# mit_radar_r2_layout.net
KiCad netlist of a schematic drawn in EAGLE
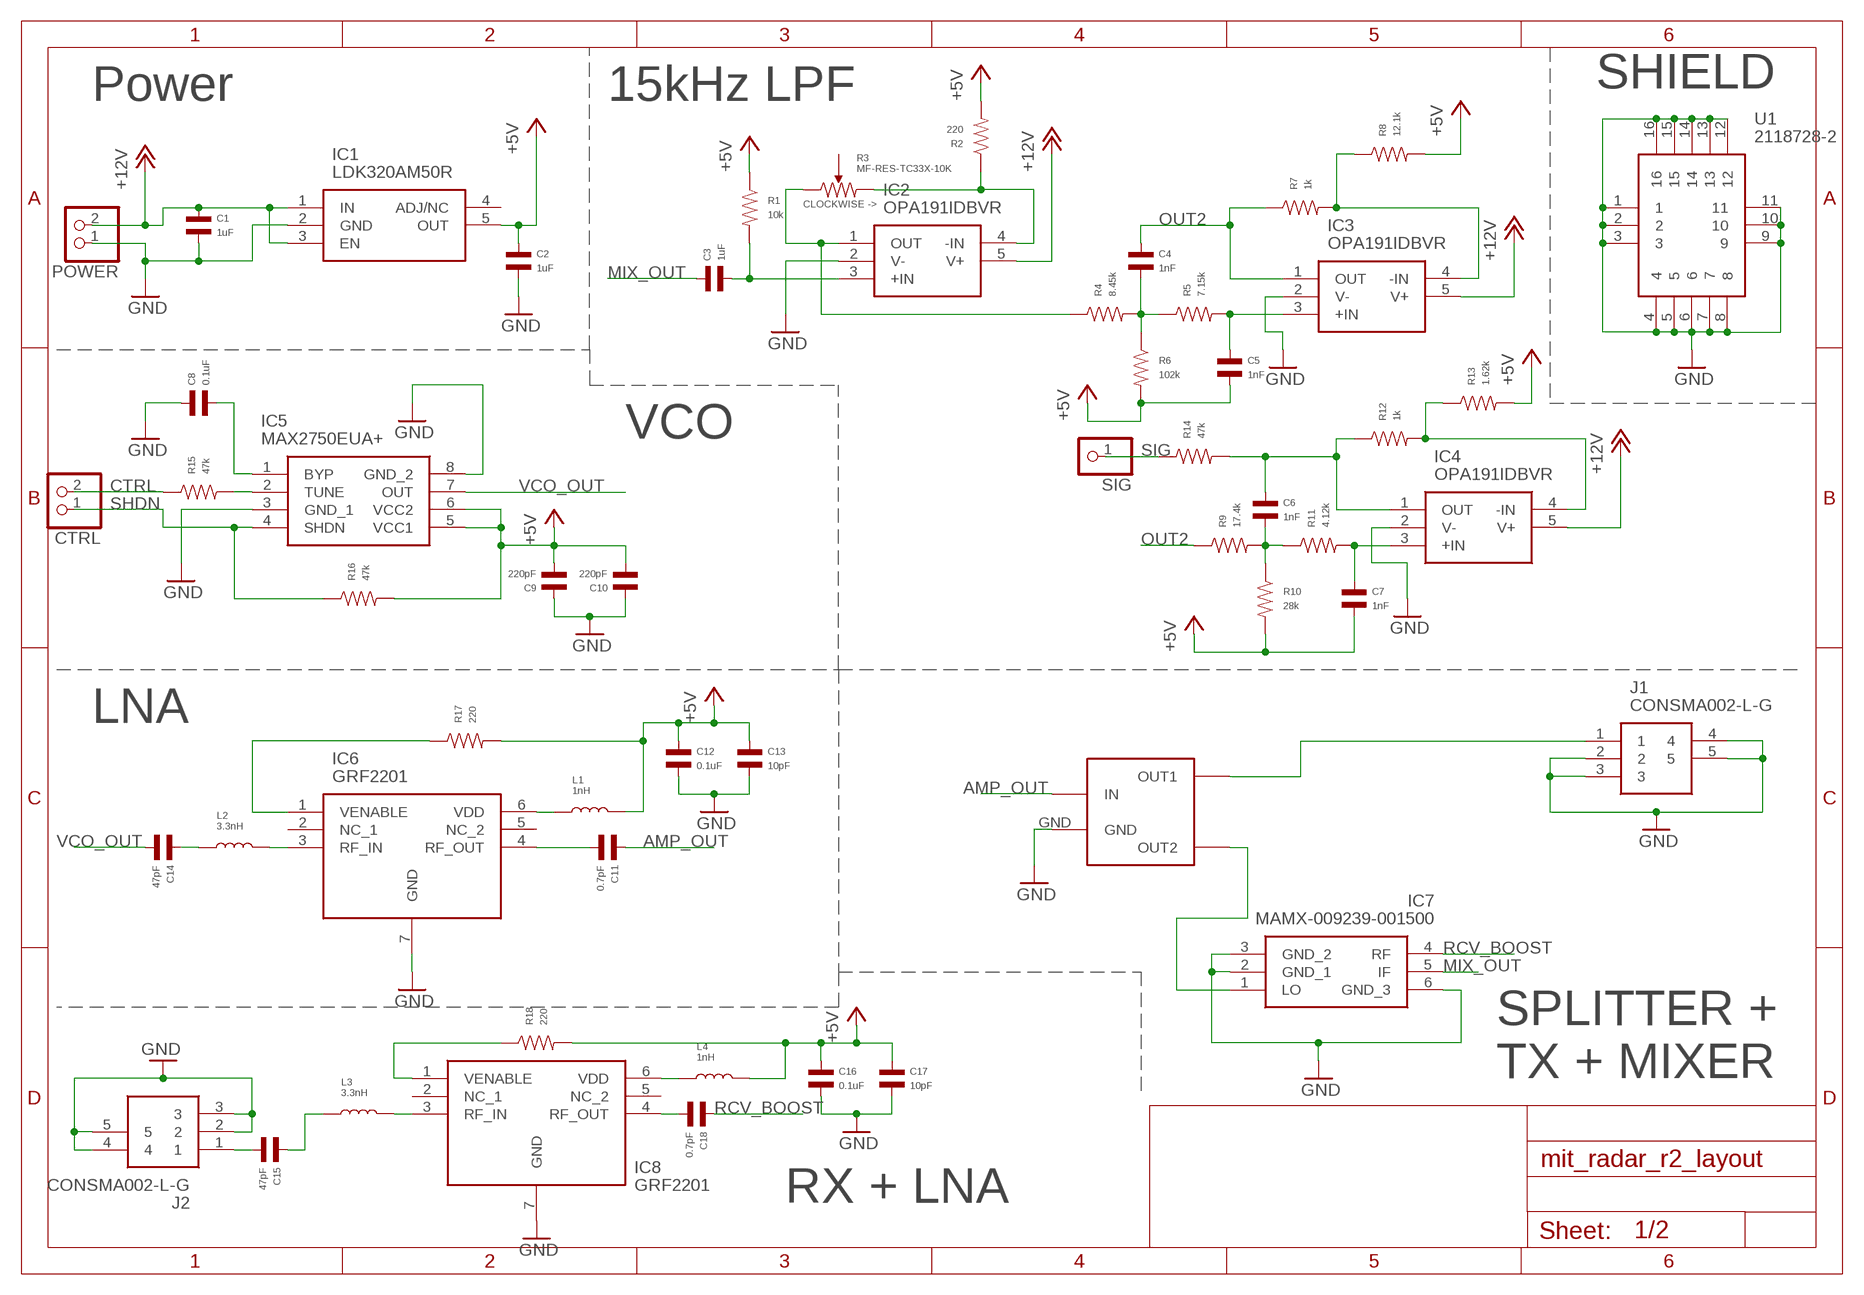
[diagram p0: schematic, sheet 1]
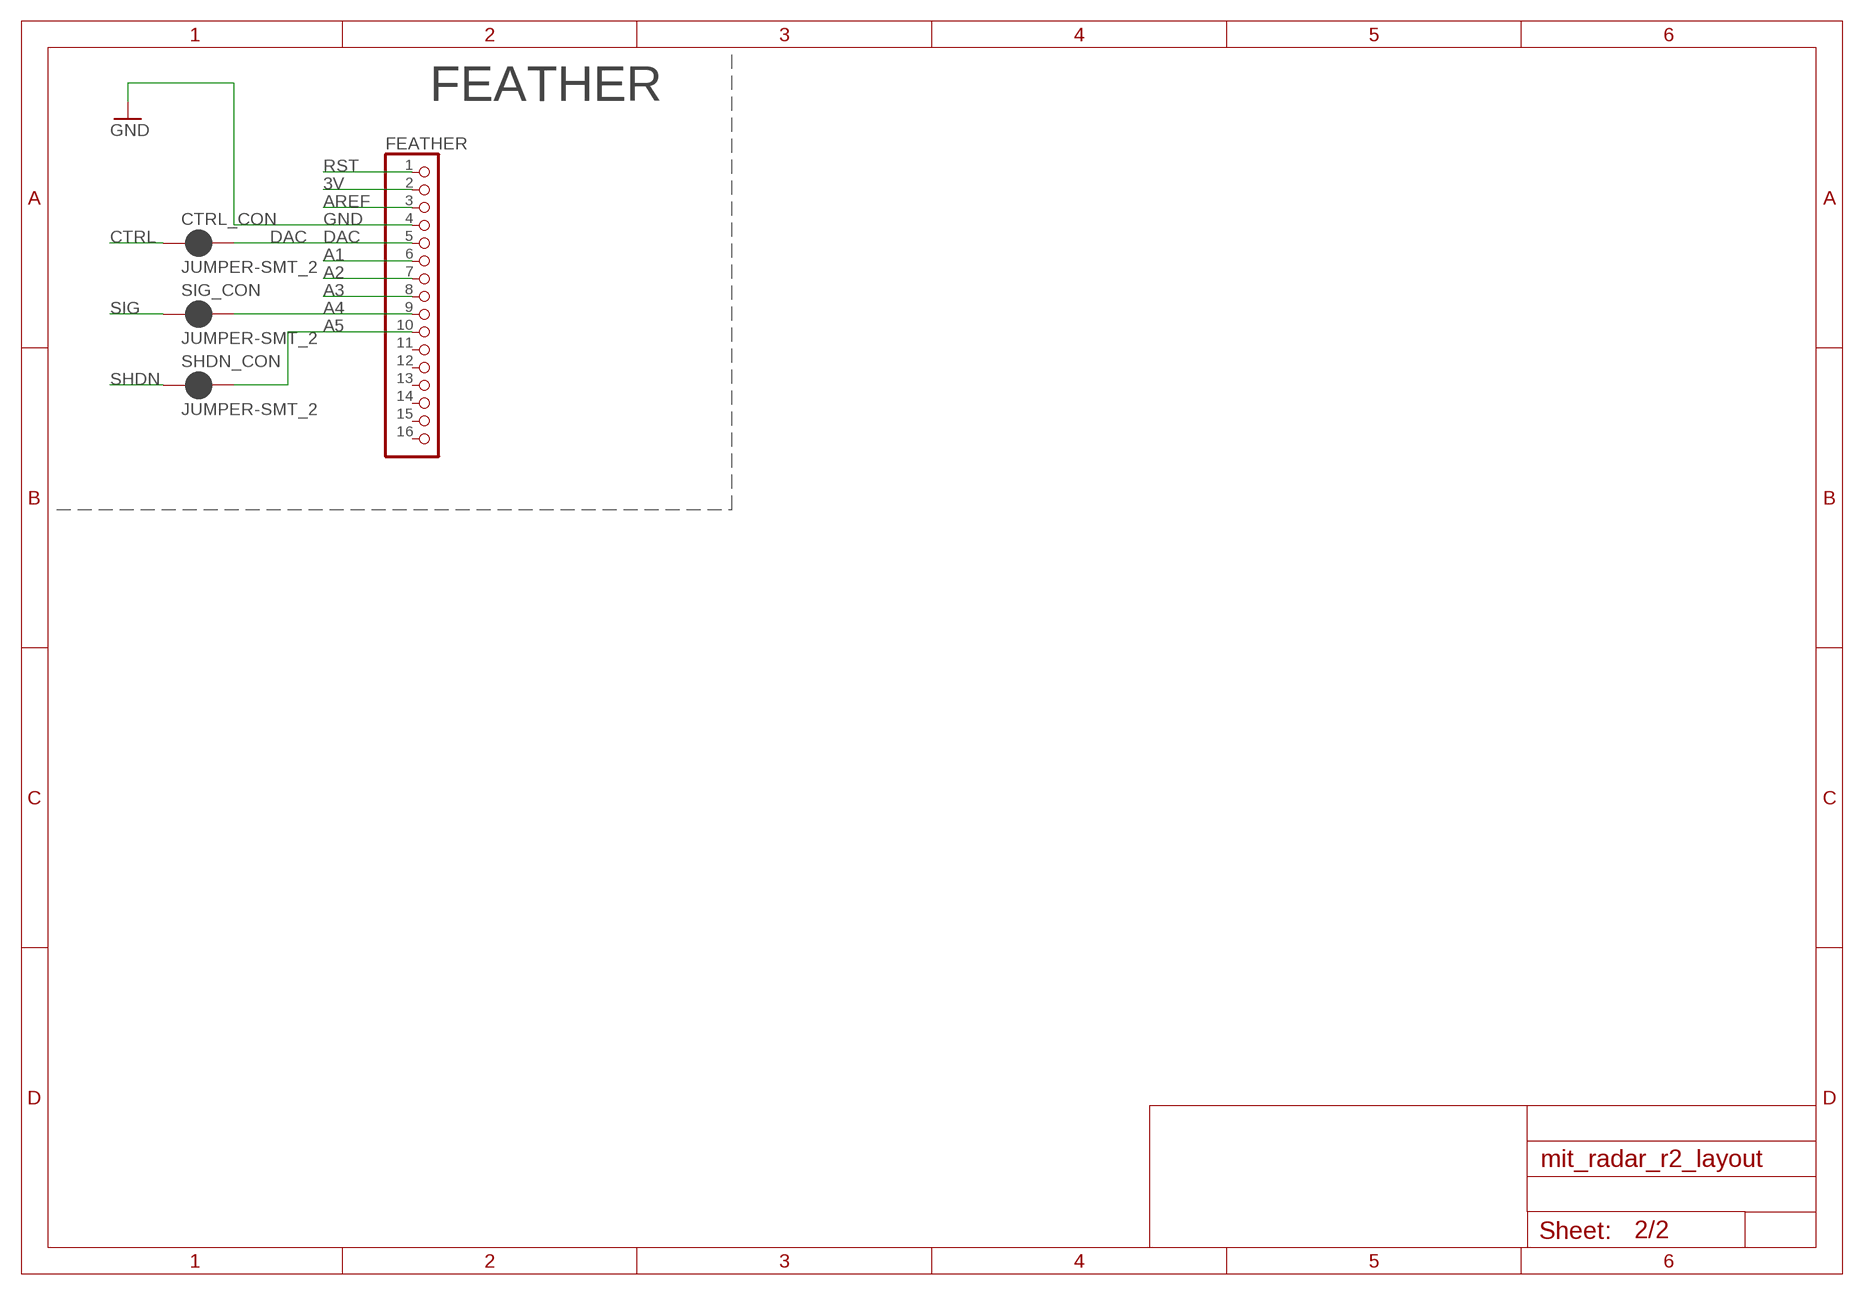
[diagram p1: schematic, sheet 2]

(export (version "E")
  (design (tool "Eeschema 10.0.6"))
  (components
    (comp (ref "C1")
      (value "1uF")
      (footprint "eagle-import:C0402")
      (libsource (lib "eagle-import") (part "CAPACITOR_NP_0402"))
    )
    (comp (ref "C2")
      (value "1uF")
      (footprint "eagle-import:C0402")
      (libsource (lib "eagle-import") (part "CAPACITOR_NP_0402"))
    )
    (comp (ref "C3")
      (value "1uF")
      (footprint "eagle-import:C0402")
      (libsource (lib "eagle-import") (part "CAPACITOR_NP_0402"))
    )
    (comp (ref "C4")
      (value "1nF")
      (footprint "eagle-import:C0402")
      (libsource (lib "eagle-import") (part "CAPACITOR_NP_0402"))
    )
    (comp (ref "C5")
      (value "1nF")
      (footprint "eagle-import:C0402")
      (libsource (lib "eagle-import") (part "CAPACITOR_NP_0402"))
    )
    (comp (ref "C6")
      (value "1nF")
      (footprint "eagle-import:C0402")
      (libsource (lib "eagle-import") (part "CAPACITOR_NP_0402"))
    )
    (comp (ref "C7")
      (value "1nF")
      (footprint "eagle-import:C0402")
      (libsource (lib "eagle-import") (part "CAPACITOR_NP_0402"))
    )
    (comp (ref "C8")
      (value "0.1uF")
      (footprint "eagle-import:C0402")
      (libsource (lib "eagle-import") (part "CAPACITOR_NP_0402"))
    )
    (comp (ref "C9")
      (value "220pF")
      (footprint "eagle-import:C0402")
      (libsource (lib "eagle-import") (part "CAPACITOR_NP_0402"))
    )
    (comp (ref "C10")
      (value "220pF")
      (footprint "eagle-import:C0402")
      (libsource (lib "eagle-import") (part "CAPACITOR_NP_0402"))
    )
    (comp (ref "C11")
      (value "0.7pF")
      (footprint "eagle-import:C0402")
      (libsource (lib "eagle-import") (part "CAPACITOR_NP_0402"))
    )
    (comp (ref "C12")
      (value "0.1uF")
      (footprint "eagle-import:C0402")
      (libsource (lib "eagle-import") (part "CAPACITOR_NP_0402"))
    )
    (comp (ref "C13")
      (value "10pF")
      (footprint "eagle-import:C0402")
      (libsource (lib "eagle-import") (part "CAPACITOR_NP_0402"))
    )
    (comp (ref "C14")
      (value "47pF")
      (footprint "eagle-import:C0402")
      (libsource (lib "eagle-import") (part "CAPACITOR_NP_0402"))
    )
    (comp (ref "C15")
      (value "47pF")
      (footprint "eagle-import:C0402")
      (libsource (lib "eagle-import") (part "CAPACITOR_NP_0402"))
    )
    (comp (ref "C16")
      (value "0.1uF")
      (footprint "eagle-import:C0402")
      (libsource (lib "eagle-import") (part "CAPACITOR_NP_0402"))
    )
    (comp (ref "C17")
      (value "10pF")
      (footprint "eagle-import:C0402")
      (libsource (lib "eagle-import") (part "CAPACITOR_NP_0402"))
    )
    (comp (ref "C18")
      (value "0.7pF")
      (footprint "eagle-import:C0402")
      (libsource (lib "eagle-import") (part "CAPACITOR_NP_0402"))
    )
    (comp (ref "CTRL")
      (value "PINHD-1X2")
      (footprint "eagle-import:1X02")
      (libsource (lib "eagle-import") (part "PINHD-1X2"))
    )
    (comp (ref "IC1")
      (value "LDK320AM50R")
      (footprint "eagle-import:SOT95P280X145-5N")
      (fields (field (name "MOUSER_PART_NUMBER") "511-LDK320AM50R"))
      (libsource (lib "eagle-import") (part "LDK320AM50R"))
    )
    (comp (ref "IC2")
      (value "OPA191IDBVR")
      (footprint "eagle-import:SOT95P280X145-5N")
      (fields (field (name "MOUSER_PART_NUMBER") "595-OPA191IDBVR"))
      (libsource (lib "eagle-import") (part "OPA191IDBVR"))
    )
    (comp (ref "IC3")
      (value "OPA191IDBVR")
      (footprint "eagle-import:SOT95P280X145-5N")
      (fields (field (name "MOUSER_PART_NUMBER") "595-OPA191IDBVR"))
      (libsource (lib "eagle-import") (part "OPA191IDBVR"))
    )
    (comp (ref "IC4")
      (value "OPA191IDBVR")
      (footprint "eagle-import:SOT95P280X145-5N")
      (fields (field (name "MOUSER_PART_NUMBER") "595-OPA191IDBVR"))
      (libsource (lib "eagle-import") (part "OPA191IDBVR"))
    )
    (comp (ref "IC5")
      (value "MAX2750EUA+")
      (footprint "eagle-import:SOP65P490X110-8N")
      (fields (field (name "MOUSER_PART_NUMBER") "700-MAX2750EUA") (field (name "RS_PART_NUMBER") "1898516P"))
      (libsource (lib "eagle-import") (part "MAX2750EUA+"))
    )
    (comp (ref "IC6")
      (value "GRF2201")
      (footprint "eagle-import:SON50P150X150X50-7N")
      (fields (field (name "MOUSER_PART_NUMBER") "459-GRF2201"))
      (libsource (lib "eagle-import") (part "GRF2201"))
    )
    (comp (ref "IC7")
      (value "MAMX-009239-001500")
      (footprint "eagle-import:MAMX009239001500")
      (fields (field (name "MOUSER_PART_NUMBER") "937-MAMX-9239-001500"))
      (libsource (lib "eagle-import") (part "MAMX-009239-001500"))
    )
    (comp (ref "IC8")
      (value "GRF2201")
      (footprint "eagle-import:SON50P150X150X50-7N")
      (fields (field (name "MOUSER_PART_NUMBER") "459-GRF2201"))
      (libsource (lib "eagle-import") (part "GRF2201"))
    )
    (comp (ref "J1")
      (value "CONSMA002-L-G")
      (footprint "eagle-import:CONSMA002LG")
      (fields (field (name "MOUSER_PART_NUMBER") "712-CONSMA002-L-G"))
      (libsource (lib "eagle-import") (part "CONSMA002-L-G"))
    )
    (comp (ref "J2")
      (value "CONSMA002-L-G")
      (footprint "eagle-import:CONSMA002LG")
      (fields (field (name "MOUSER_PART_NUMBER") "712-CONSMA002-L-G"))
      (libsource (lib "eagle-import") (part "CONSMA002-L-G"))
    )
    (comp (ref "L1")
      (value "1nH")
      (footprint "eagle-import:L0402")
      (libsource (lib "eagle-import") (part "INDUCTOR_0402"))
    )
    (comp (ref "L2")
      (value "3.3nH")
      (footprint "eagle-import:L0402")
      (libsource (lib "eagle-import") (part "INDUCTOR_0402"))
    )
    (comp (ref "L3")
      (value "3.3nH")
      (footprint "eagle-import:L0402")
      (libsource (lib "eagle-import") (part "INDUCTOR_0402"))
    )
    (comp (ref "L4")
      (value "1nH")
      (footprint "eagle-import:L0402")
      (libsource (lib "eagle-import") (part "INDUCTOR_0402"))
    )
    (comp (ref "POWER")
      (value "PINHD-1X2")
      (footprint "eagle-import:1X02")
      (libsource (lib "eagle-import") (part "PINHD-1X2"))
    )
    (comp (ref "R1")
      (value "10k")
      (footprint "eagle-import:R0402")
      (libsource (lib "eagle-import") (part "RESISTOR_0402"))
    )
    (comp (ref "R2")
      (value "220")
      (footprint "eagle-import:R0402")
      (libsource (lib "eagle-import") (part "RESISTOR_0402"))
    )
    (comp (ref "R3")
      (value "MF-RES-TC33X-10K")
      (footprint "eagle-import:TC33")
      (fields (field (name "HOUSEPART") "YES") (field (name "TOLERANCE") "25%"))
      (libsource (lib "eagle-import") (part "POTENTIOMETER_TC33_10K"))
    )
    (comp (ref "R4")
      (value "8.45k")
      (footprint "eagle-import:R0402")
      (libsource (lib "eagle-import") (part "RESISTOR_0402"))
    )
    (comp (ref "R5")
      (value "7.15k")
      (footprint "eagle-import:R0402")
      (libsource (lib "eagle-import") (part "RESISTOR_0402"))
    )
    (comp (ref "R6")
      (value "102k")
      (footprint "eagle-import:R0402")
      (libsource (lib "eagle-import") (part "RESISTOR_0402"))
    )
    (comp (ref "R7")
      (value "1k")
      (footprint "eagle-import:R0402")
      (libsource (lib "eagle-import") (part "RESISTOR_0402"))
    )
    (comp (ref "R8")
      (value "12.1k")
      (footprint "eagle-import:R0402")
      (libsource (lib "eagle-import") (part "RESISTOR_0402"))
    )
    (comp (ref "R9")
      (value "17.4k")
      (footprint "eagle-import:R0402")
      (libsource (lib "eagle-import") (part "RESISTOR_0402"))
    )
    (comp (ref "R10")
      (value "28k")
      (footprint "eagle-import:R0402")
      (libsource (lib "eagle-import") (part "RESISTOR_0402"))
    )
    (comp (ref "R11")
      (value "4.12k")
      (footprint "eagle-import:R0402")
      (libsource (lib "eagle-import") (part "RESISTOR_0402"))
    )
    (comp (ref "R12")
      (value "1k")
      (footprint "eagle-import:R0402")
      (libsource (lib "eagle-import") (part "RESISTOR_0402"))
    )
    (comp (ref "R13")
      (value "1.62k")
      (footprint "eagle-import:R0402")
      (libsource (lib "eagle-import") (part "RESISTOR_0402"))
    )
    (comp (ref "R14")
      (value "47k")
      (footprint "eagle-import:R0402")
      (libsource (lib "eagle-import") (part "RESISTOR_0402"))
    )
    (comp (ref "R15")
      (value "47k")
      (footprint "eagle-import:R0402")
      (libsource (lib "eagle-import") (part "RESISTOR_0402"))
    )
    (comp (ref "R16")
      (value "47k")
      (footprint "eagle-import:R0402")
      (libsource (lib "eagle-import") (part "RESISTOR_0402"))
    )
    (comp (ref "R17")
      (value "220")
      (footprint "eagle-import:R0402")
      (libsource (lib "eagle-import") (part "RESISTOR_0402"))
    )
    (comp (ref "R18")
      (value "220")
      (footprint "eagle-import:R0402")
      (libsource (lib "eagle-import") (part "RESISTOR_0402"))
    )
    (comp (ref "SIG")
      (value "PINHD-1X1")
      (footprint "eagle-import:1X01")
      (libsource (lib "eagle-import") (part "PINHD-1X1"))
    )
    (comp (ref "U$1")
      (value "PS3216GT2-R50-T1")
      (footprint "eagle-import:PS3216GT2-R50-T1")
      (libsource (lib "eagle-import") (part "PS3216GT2-R50-T1"))
    )
    (comp (ref "U1")
      (value "2118728-2")
      (footprint "eagle-import:21187282")
      (fields (field (name "MOUSER_PART_NUMBER") "571-2118728-2") (field (name "RS_PART_NUMBER") "1720955"))
      (libsource (lib "eagle-import") (part "2118728-2"))
    )
    (comp (ref "CTRL_CON")
      (value "JUMPER-SMT_2")
      (footprint "eagle-import:SMT-JUMPER_2_NC_PASTE_NO-SILK")
      (libsource (lib "eagle-import") (part "JUMPER-SMT_2_NC_PASTE_NO-SILK"))
    )
    (comp (ref "FEATHER")
      (value "PINHD-1X16")
      (footprint "eagle-import:1X16")
      (libsource (lib "eagle-import") (part "PINHD-1X16"))
    )
    (comp (ref "SHDN_CON")
      (value "JUMPER-SMT_2")
      (footprint "eagle-import:SMT-JUMPER_2_NC_PASTE_NO-SILK")
      (libsource (lib "eagle-import") (part "JUMPER-SMT_2_NC_PASTE_NO-SILK"))
    )
    (comp (ref "SIG_CON")
      (value "JUMPER-SMT_2")
      (footprint "eagle-import:SMT-JUMPER_2_NC_PASTE_NO-SILK")
      (libsource (lib "eagle-import") (part "JUMPER-SMT_2_NC_PASTE_NO-SILK"))
    )
  )
  (nets
    (net (code "1") (name "+5V") (class "Default")
      (node (ref "C10") (pin "P$2") (pinfunction "P$2_P$2") (pintype "passive"))
      (node (ref "C12") (pin "P$1") (pinfunction "P$1_P$1") (pintype "passive"))
      (node (ref "C13") (pin "P$1") (pinfunction "P$1_P$1") (pintype "passive"))
      (node (ref "C16") (pin "P$1") (pinfunction "P$1_P$1") (pintype "passive"))
      (node (ref "C17") (pin "P$1") (pinfunction "P$1_P$1") (pintype "passive"))
      (node (ref "C2") (pin "P$1") (pinfunction "P$1_P$1") (pintype "passive"))
      (node (ref "C5") (pin "P$2") (pinfunction "P$2_P$2") (pintype "passive"))
      (node (ref "C7") (pin "P$2") (pinfunction "P$2_P$2") (pintype "passive"))
      (node (ref "C9") (pin "P$2") (pinfunction "P$2_P$2") (pintype "passive"))
      (node (ref "IC1") (pin "5") (pinfunction "OUT_5") (pintype "bidirectional"))
      (node (ref "IC5") (pin "5") (pinfunction "VCC1_5") (pintype "bidirectional"))
      (node (ref "IC5") (pin "6") (pinfunction "VCC2_6") (pintype "bidirectional"))
      (node (ref "L1") (pin "P$2") (pinfunction "P$2_P$2") (pintype "passive"))
      (node (ref "L4") (pin "P$2") (pinfunction "P$2_P$2") (pintype "passive"))
      (node (ref "R1") (pin "P$1") (pinfunction "P$1_P$1") (pintype "passive"))
      (node (ref "R10") (pin "P$2") (pinfunction "P$2_P$2") (pintype "passive"))
      (node (ref "R13") (pin "P$2") (pinfunction "P$2_P$2") (pintype "passive"))
      (node (ref "R16") (pin "P$2") (pinfunction "P$2_P$2") (pintype "passive"))
      (node (ref "R17") (pin "P$2") (pinfunction "P$2_P$2") (pintype "passive"))
      (node (ref "R18") (pin "P$2") (pinfunction "P$2_P$2") (pintype "passive"))
      (node (ref "R2") (pin "P$2") (pinfunction "P$2_P$2") (pintype "passive"))
      (node (ref "R6") (pin "P$2") (pinfunction "P$2_P$2") (pintype "passive"))
      (node (ref "R8") (pin "P$2") (pinfunction "P$2_P$2") (pintype "passive"))
    )
    (net (code "2") (name "+12V") (class "Default")
      (node (ref "C1") (pin "P$1") (pinfunction "P$1_P$1") (pintype "passive"))
      (node (ref "IC1") (pin "1") (pinfunction "IN_1") (pintype "bidirectional"))
      (node (ref "IC1") (pin "3") (pinfunction "EN_3") (pintype "bidirectional"))
      (node (ref "IC2") (pin "5") (pinfunction "V+_5") (pintype "bidirectional"))
      (node (ref "IC3") (pin "5") (pinfunction "V+_5") (pintype "bidirectional"))
      (node (ref "IC4") (pin "5") (pinfunction "V+_5") (pintype "bidirectional"))
      (node (ref "POWER") (pin "2") (pinfunction "2_2") (pintype "passive"))
    )
    (net (code "3") (name "3V") (class "Default")
      (node (ref "FEATHER") (pin "2") (pinfunction "2_2") (pintype "passive"))
    )
    (net (code "4") (name "A1") (class "Default")
      (node (ref "FEATHER") (pin "6") (pinfunction "6_6") (pintype "passive"))
    )
    (net (code "5") (name "A2") (class "Default")
      (node (ref "FEATHER") (pin "7") (pinfunction "7_7") (pintype "passive"))
    )
    (net (code "6") (name "A3") (class "Default")
      (node (ref "FEATHER") (pin "8") (pinfunction "8_8") (pintype "passive"))
    )
    (net (code "7") (name "A4") (class "Default")
      (node (ref "FEATHER") (pin "9") (pinfunction "9_9") (pintype "passive"))
      (node (ref "SIG_CON") (pin "2") (pinfunction "2_2") (pintype "passive"))
    )
    (net (code "8") (name "A5") (class "Default")
      (node (ref "FEATHER") (pin "10") (pinfunction "10_10") (pintype "passive"))
      (node (ref "SHDN_CON") (pin "2") (pinfunction "2_2") (pintype "passive"))
    )
    (net (code "9") (name "AMP_OUT") (class "Default")
      (node (ref "C11") (pin "P$1") (pinfunction "P$1_P$1") (pintype "passive"))
      (node (ref "U$1") (pin "IN") (pinfunction "IN_IN") (pintype "bidirectional"))
    )
    (net (code "10") (name "AREF") (class "Default")
      (node (ref "FEATHER") (pin "3") (pinfunction "3_3") (pintype "passive"))
    )
    (net (code "11") (name "CTRL") (class "Default")
      (node (ref "CTRL") (pin "2") (pinfunction "2_2") (pintype "passive"))
      (node (ref "CTRL_CON") (pin "1") (pinfunction "1_1") (pintype "passive"))
      (node (ref "R15") (pin "P$1") (pinfunction "P$1_P$1") (pintype "passive"))
    )
    (net (code "12") (name "DAC") (class "Default")
      (node (ref "CTRL_CON") (pin "2") (pinfunction "2_2") (pintype "passive"))
      (node (ref "FEATHER") (pin "5") (pinfunction "5_5") (pintype "passive"))
    )
    (net (code "13") (name "GND") (class "Default")
      (node (ref "C1") (pin "P$2") (pinfunction "P$2_P$2") (pintype "passive"))
      (node (ref "C10") (pin "P$1") (pinfunction "P$1_P$1") (pintype "passive"))
      (node (ref "C12") (pin "P$2") (pinfunction "P$2_P$2") (pintype "passive"))
      (node (ref "C13") (pin "P$2") (pinfunction "P$2_P$2") (pintype "passive"))
      (node (ref "C16") (pin "P$2") (pinfunction "P$2_P$2") (pintype "passive"))
      (node (ref "C17") (pin "P$2") (pinfunction "P$2_P$2") (pintype "passive"))
      (node (ref "C2") (pin "P$2") (pinfunction "P$2_P$2") (pintype "passive"))
      (node (ref "C8") (pin "P$1") (pinfunction "P$1_P$1") (pintype "passive"))
      (node (ref "C9") (pin "P$1") (pinfunction "P$1_P$1") (pintype "passive"))
      (node (ref "FEATHER") (pin "4") (pinfunction "4_4") (pintype "passive"))
      (node (ref "IC1") (pin "2") (pinfunction "GND_2") (pintype "bidirectional"))
      (node (ref "IC2") (pin "2") (pinfunction "V-_2") (pintype "bidirectional"))
      (node (ref "IC3") (pin "2") (pinfunction "V-_2") (pintype "bidirectional"))
      (node (ref "IC4") (pin "2") (pinfunction "V-_2") (pintype "bidirectional"))
      (node (ref "IC5") (pin "3") (pinfunction "GND_1_3") (pintype "bidirectional"))
      (node (ref "IC5") (pin "8") (pinfunction "GND_2_8") (pintype "bidirectional"))
      (node (ref "IC6") (pin "7") (pinfunction "GND_7") (pintype "bidirectional"))
      (node (ref "IC7") (pin "2") (pinfunction "GND_1_2") (pintype "bidirectional"))
      (node (ref "IC7") (pin "3") (pinfunction "GND_2_3") (pintype "bidirectional"))
      (node (ref "IC7") (pin "6") (pinfunction "GND_3_6") (pintype "bidirectional"))
      (node (ref "IC8") (pin "7") (pinfunction "GND_7") (pintype "bidirectional"))
      (node (ref "J1") (pin "2") (pinfunction "2_2") (pintype "bidirectional"))
      (node (ref "J1") (pin "3") (pinfunction "3_3") (pintype "bidirectional"))
      (node (ref "J1") (pin "4") (pinfunction "4_4") (pintype "bidirectional"))
      (node (ref "J1") (pin "5") (pinfunction "5_5") (pintype "bidirectional"))
      (node (ref "J2") (pin "2") (pinfunction "2_2") (pintype "bidirectional"))
      (node (ref "J2") (pin "3") (pinfunction "3_3") (pintype "bidirectional"))
      (node (ref "J2") (pin "4") (pinfunction "4_4") (pintype "bidirectional"))
      (node (ref "J2") (pin "5") (pinfunction "5_5") (pintype "bidirectional"))
      (node (ref "POWER") (pin "1") (pinfunction "1_1") (pintype "passive"))
      (node (ref "U$1") (pin "GND") (pinfunction "GND_GND") (pintype "bidirectional"))
      (node (ref "U1") (pin "1") (pinfunction "1_1") (pintype "bidirectional"))
      (node (ref "U1") (pin "10") (pinfunction "10_10") (pintype "bidirectional"))
      (node (ref "U1") (pin "11") (pinfunction "11_11") (pintype "bidirectional"))
      (node (ref "U1") (pin "12") (pinfunction "12_12") (pintype "bidirectional"))
      (node (ref "U1") (pin "13") (pinfunction "13_13") (pintype "bidirectional"))
      (node (ref "U1") (pin "14") (pinfunction "14_14") (pintype "bidirectional"))
      (node (ref "U1") (pin "15") (pinfunction "15_15") (pintype "bidirectional"))
      (node (ref "U1") (pin "16") (pinfunction "16_16") (pintype "bidirectional"))
      (node (ref "U1") (pin "2") (pinfunction "2_2") (pintype "bidirectional"))
      (node (ref "U1") (pin "3") (pinfunction "3_3") (pintype "bidirectional"))
      (node (ref "U1") (pin "4") (pinfunction "4_4") (pintype "bidirectional"))
      (node (ref "U1") (pin "5") (pinfunction "5_5") (pintype "bidirectional"))
      (node (ref "U1") (pin "6") (pinfunction "6_6") (pintype "bidirectional"))
      (node (ref "U1") (pin "7") (pinfunction "7_7") (pintype "bidirectional"))
      (node (ref "U1") (pin "8") (pinfunction "8_8") (pintype "bidirectional"))
      (node (ref "U1") (pin "9") (pinfunction "9_9") (pintype "bidirectional"))
    )
    (net (code "14") (name "MIX_OUT") (class "Default")
      (node (ref "C3") (pin "P$1") (pinfunction "P$1_P$1") (pintype "passive"))
      (node (ref "IC7") (pin "5") (pinfunction "IF_5") (pintype "bidirectional"))
    )
    (net (code "15") (name "Net-(C4-PadP$2)") (class "Default")
      (node (ref "C4") (pin "P$2") (pinfunction "P$2_P$2") (pintype "passive"))
      (node (ref "R4") (pin "P$2") (pinfunction "P$2_P$2") (pintype "passive"))
      (node (ref "R5") (pin "P$1") (pinfunction "P$1_P$1") (pintype "passive"))
      (node (ref "R6") (pin "P$1") (pinfunction "P$1_P$1") (pintype "passive"))
    )
    (net (code "16") (name "Net-(C6-PadP$2)") (class "Default")
      (node (ref "C6") (pin "P$2") (pinfunction "P$2_P$2") (pintype "passive"))
      (node (ref "R10") (pin "P$1") (pinfunction "P$1_P$1") (pintype "passive"))
      (node (ref "R11") (pin "P$1") (pinfunction "P$1_P$1") (pintype "passive"))
      (node (ref "R9") (pin "P$2") (pinfunction "P$2_P$2") (pintype "passive"))
    )
    (net (code "17") (name "Net-(C14-PadP$1)") (class "Default")
      (node (ref "C14") (pin "P$1") (pinfunction "P$1_P$1") (pintype "passive"))
      (node (ref "L2") (pin "P$1") (pinfunction "P$1_P$1") (pintype "passive"))
    )
    (net (code "18") (name "Net-(C15-PadP$1)") (class "Default")
      (node (ref "C15") (pin "P$1") (pinfunction "P$1_P$1") (pintype "passive"))
      (node (ref "L3") (pin "P$1") (pinfunction "P$1_P$1") (pintype "passive"))
    )
    (net (code "19") (name "Net-(C15-PadP$2)") (class "Default")
      (node (ref "C15") (pin "P$2") (pinfunction "P$2_P$2") (pintype "passive"))
      (node (ref "J2") (pin "1") (pinfunction "1_1") (pintype "bidirectional"))
    )
    (net (code "20") (name "Net-(IC2-+IN)") (class "Default")
      (node (ref "C3") (pin "P$2") (pinfunction "P$2_P$2") (pintype "passive"))
      (node (ref "IC2") (pin "3") (pinfunction "+IN_3") (pintype "bidirectional"))
      (node (ref "R1") (pin "P$2") (pinfunction "P$2_P$2") (pintype "passive"))
    )
    (net (code "21") (name "Net-(IC2--IN)") (class "Default")
      (node (ref "IC2") (pin "4") (pinfunction "-IN_4") (pintype "bidirectional"))
      (node (ref "R2") (pin "P$1") (pinfunction "P$1_P$1") (pintype "passive"))
      (node (ref "R3") (pin "P$3") (pinfunction "P$3_P$3") (pintype "passive"))
    )
    (net (code "22") (name "Net-(IC2-OUT)") (class "Default")
      (node (ref "IC2") (pin "1") (pinfunction "OUT_1") (pintype "bidirectional"))
      (node (ref "R3") (pin "P$1") (pinfunction "P$1_P$1") (pintype "passive"))
      (node (ref "R4") (pin "P$1") (pinfunction "P$1_P$1") (pintype "passive"))
    )
    (net (code "23") (name "Net-(IC3-+IN)") (class "Default")
      (node (ref "C5") (pin "P$1") (pinfunction "P$1_P$1") (pintype "passive"))
      (node (ref "IC3") (pin "3") (pinfunction "+IN_3") (pintype "bidirectional"))
      (node (ref "R5") (pin "P$2") (pinfunction "P$2_P$2") (pintype "passive"))
    )
    (net (code "24") (name "Net-(IC3--IN)") (class "Default")
      (node (ref "IC3") (pin "4") (pinfunction "-IN_4") (pintype "bidirectional"))
      (node (ref "R7") (pin "P$2") (pinfunction "P$2_P$2") (pintype "passive"))
      (node (ref "R8") (pin "P$1") (pinfunction "P$1_P$1") (pintype "passive"))
    )
    (net (code "25") (name "Net-(IC4-+IN)") (class "Default")
      (node (ref "C7") (pin "P$1") (pinfunction "P$1_P$1") (pintype "passive"))
      (node (ref "IC4") (pin "3") (pinfunction "+IN_3") (pintype "bidirectional"))
      (node (ref "R11") (pin "P$2") (pinfunction "P$2_P$2") (pintype "passive"))
    )
    (net (code "26") (name "Net-(IC4--IN)") (class "Default")
      (node (ref "IC4") (pin "4") (pinfunction "-IN_4") (pintype "bidirectional"))
      (node (ref "R12") (pin "P$2") (pinfunction "P$2_P$2") (pintype "passive"))
      (node (ref "R13") (pin "P$1") (pinfunction "P$1_P$1") (pintype "passive"))
    )
    (net (code "27") (name "Net-(IC4-OUT)") (class "Default")
      (node (ref "C6") (pin "P$1") (pinfunction "P$1_P$1") (pintype "passive"))
      (node (ref "IC4") (pin "1") (pinfunction "OUT_1") (pintype "bidirectional"))
      (node (ref "R12") (pin "P$1") (pinfunction "P$1_P$1") (pintype "passive"))
      (node (ref "R14") (pin "P$2") (pinfunction "P$2_P$2") (pintype "passive"))
    )
    (net (code "28") (name "Net-(IC5-BYP)") (class "Default")
      (node (ref "C8") (pin "P$2") (pinfunction "P$2_P$2") (pintype "passive"))
      (node (ref "IC5") (pin "1") (pinfunction "BYP_1") (pintype "bidirectional"))
    )
    (net (code "29") (name "Net-(IC5-TUNE)") (class "Default")
      (node (ref "IC5") (pin "2") (pinfunction "TUNE_2") (pintype "bidirectional"))
      (node (ref "R15") (pin "P$2") (pinfunction "P$2_P$2") (pintype "passive"))
    )
    (net (code "30") (name "Net-(IC6-RF_IN)") (class "Default")
      (node (ref "IC6") (pin "3") (pinfunction "RF_IN_3") (pintype "bidirectional"))
      (node (ref "L2") (pin "P$2") (pinfunction "P$2_P$2") (pintype "passive"))
    )
    (net (code "31") (name "Net-(IC6-RF_OUT)") (class "Default")
      (node (ref "C11") (pin "P$2") (pinfunction "P$2_P$2") (pintype "passive"))
      (node (ref "IC6") (pin "4") (pinfunction "RF_OUT_4") (pintype "bidirectional"))
    )
    (net (code "32") (name "Net-(IC6-VDD)") (class "Default")
      (node (ref "IC6") (pin "6") (pinfunction "VDD_6") (pintype "bidirectional"))
      (node (ref "L1") (pin "P$1") (pinfunction "P$1_P$1") (pintype "passive"))
    )
    (net (code "33") (name "Net-(IC6-VENABLE)") (class "Default")
      (node (ref "IC6") (pin "1") (pinfunction "VENABLE_1") (pintype "bidirectional"))
      (node (ref "R17") (pin "P$1") (pinfunction "P$1_P$1") (pintype "passive"))
    )
    (net (code "34") (name "Net-(IC7-LO)") (class "Default")
      (node (ref "IC7") (pin "1") (pinfunction "LO_1") (pintype "bidirectional"))
      (node (ref "U$1") (pin "OUT2") (pinfunction "OUT2_OUT2") (pintype "bidirectional"))
    )
    (net (code "35") (name "Net-(IC8-RF_IN)") (class "Default")
      (node (ref "IC8") (pin "3") (pinfunction "RF_IN_3") (pintype "bidirectional"))
      (node (ref "L3") (pin "P$2") (pinfunction "P$2_P$2") (pintype "passive"))
    )
    (net (code "36") (name "Net-(IC8-RF_OUT)") (class "Default")
      (node (ref "C18") (pin "P$2") (pinfunction "P$2_P$2") (pintype "passive"))
      (node (ref "IC8") (pin "4") (pinfunction "RF_OUT_4") (pintype "bidirectional"))
    )
    (net (code "37") (name "Net-(IC8-VDD)") (class "Default")
      (node (ref "IC8") (pin "6") (pinfunction "VDD_6") (pintype "bidirectional"))
      (node (ref "L4") (pin "P$1") (pinfunction "P$1_P$1") (pintype "passive"))
    )
    (net (code "38") (name "Net-(IC8-VENABLE)") (class "Default")
      (node (ref "IC8") (pin "1") (pinfunction "VENABLE_1") (pintype "bidirectional"))
      (node (ref "R18") (pin "P$1") (pinfunction "P$1_P$1") (pintype "passive"))
    )
    (net (code "39") (name "Net-(J1-Pad1)") (class "Default")
      (node (ref "J1") (pin "1") (pinfunction "1_1") (pintype "bidirectional"))
      (node (ref "U$1") (pin "OUT1") (pinfunction "OUT1_OUT1") (pintype "bidirectional"))
    )
    (net (code "40") (name "OUT2") (class "Default")
      (node (ref "C4") (pin "P$1") (pinfunction "P$1_P$1") (pintype "passive"))
      (node (ref "IC3") (pin "1") (pinfunction "OUT_1") (pintype "bidirectional"))
      (node (ref "R7") (pin "P$1") (pinfunction "P$1_P$1") (pintype "passive"))
      (node (ref "R9") (pin "P$1") (pinfunction "P$1_P$1") (pintype "passive"))
    )
    (net (code "41") (name "RCV_BOOST") (class "Default")
      (node (ref "C18") (pin "P$1") (pinfunction "P$1_P$1") (pintype "passive"))
      (node (ref "IC7") (pin "4") (pinfunction "RF_4") (pintype "bidirectional"))
    )
    (net (code "42") (name "RST") (class "Default")
      (node (ref "FEATHER") (pin "1") (pinfunction "1_1") (pintype "passive"))
    )
    (net (code "43") (name "SHDN") (class "Default")
      (node (ref "CTRL") (pin "1") (pinfunction "1_1") (pintype "passive"))
      (node (ref "IC5") (pin "4") (pinfunction "SHDN_4") (pintype "bidirectional"))
      (node (ref "R16") (pin "P$1") (pinfunction "P$1_P$1") (pintype "passive"))
      (node (ref "SHDN_CON") (pin "1") (pinfunction "1_1") (pintype "passive"))
    )
    (net (code "44") (name "SIG") (class "Default")
      (node (ref "R14") (pin "P$1") (pinfunction "P$1_P$1") (pintype "passive"))
      (node (ref "SIG") (pin "1") (pinfunction "1_1") (pintype "passive"))
      (node (ref "SIG_CON") (pin "1") (pinfunction "1_1") (pintype "passive"))
    )
    (net (code "45") (name "VCO_OUT") (class "Default")
      (node (ref "C14") (pin "P$2") (pinfunction "P$2_P$2") (pintype "passive"))
      (node (ref "IC5") (pin "7") (pinfunction "OUT_7") (pintype "bidirectional"))
    )
    (net (code "46") (name "unconnected-(FEATHER-Pad11)") (class "Default")
      (node (ref "FEATHER") (pin "11") (pinfunction "11_11") (pintype "passive"))
    )
    (net (code "47") (name "unconnected-(FEATHER-Pad12)") (class "Default")
      (node (ref "FEATHER") (pin "12") (pinfunction "12_12") (pintype "passive"))
    )
    (net (code "48") (name "unconnected-(FEATHER-Pad13)") (class "Default")
      (node (ref "FEATHER") (pin "13") (pinfunction "13_13") (pintype "passive"))
    )
    (net (code "49") (name "unconnected-(FEATHER-Pad14)") (class "Default")
      (node (ref "FEATHER") (pin "14") (pinfunction "14_14") (pintype "passive"))
    )
    (net (code "50") (name "unconnected-(FEATHER-Pad15)") (class "Default")
      (node (ref "FEATHER") (pin "15") (pinfunction "15_15") (pintype "passive"))
    )
    (net (code "51") (name "unconnected-(FEATHER-Pad16)") (class "Default")
      (node (ref "FEATHER") (pin "16") (pinfunction "16_16") (pintype "passive"))
    )
    (net (code "52") (name "unconnected-(IC1-ADJ{slash}NC-Pad4)") (class "Default")
      (node (ref "IC1") (pin "4") (pinfunction "ADJ/NC_4") (pintype "bidirectional"))
    )
    (net (code "53") (name "unconnected-(IC6-NC_1-Pad2)") (class "Default")
      (node (ref "IC6") (pin "2") (pinfunction "NC_1_2") (pintype "bidirectional"))
    )
    (net (code "54") (name "unconnected-(IC6-NC_2-Pad5)") (class "Default")
      (node (ref "IC6") (pin "5") (pinfunction "NC_2_5") (pintype "bidirectional"))
    )
    (net (code "55") (name "unconnected-(IC8-NC_1-Pad2)") (class "Default")
      (node (ref "IC8") (pin "2") (pinfunction "NC_1_2") (pintype "bidirectional"))
    )
    (net (code "56") (name "unconnected-(IC8-NC_2-Pad5)") (class "Default")
      (node (ref "IC8") (pin "5") (pinfunction "NC_2_5") (pintype "bidirectional"))
    )
    (net (code "57") (name "unconnected-(R3-PadP$2)") (class "Default")
      (node (ref "R3") (pin "P$2") (pinfunction "P$2_P$2") (pintype "passive"))
    )
  )
)
